# power.net
KiCad netlist of a schematic drawn in Altium Designer
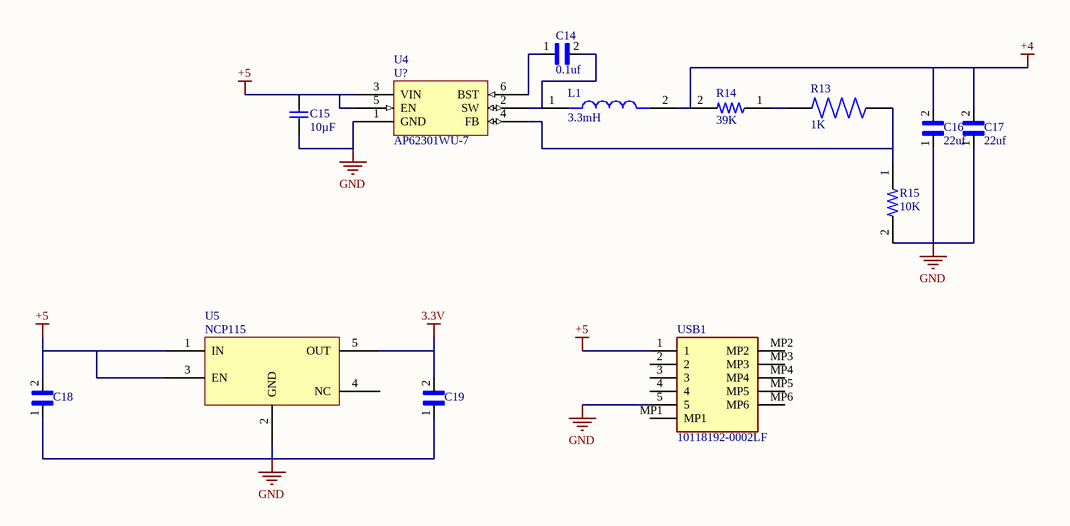
[diagram p0: power.SchDoc]

(export (version "E")
  (design (tool "Eeschema 10.0.6"))
  (components
    (comp (ref "C14")
      (value "0.1uf")
      (footprint "CAPC1608X90N")
      (description "Cap Ceramic 0.1uF 25V Y5V -20% to 80% SMD 0603 85C T/R")
      (fields (field (name "MP") "06033G104ZAT4A") (field (name "MF") "{'manufacturer': u'AVX'}"))
      (libsource (lib "SnapEDA_Library") (part "06033G104ZAT4A"))
    )
    (comp (ref "C15")
      (value "10µF")
      (footprint "CAP_0603")
      (description "10µF 10V Ceramic Capacitor X5R 0603 (1608 Metric) 0.063\" L x 0.031\" W (1.60mm x 0.80mm)")
      (fields
        (field (name "MANUFACTURER") "Samsung Electronics")
        (field (name "PART NUMBER") "CL10A106KP8NNNC")
      )
      (libsource (lib "apollo2-amaph1kk-kbr-brd") (part "CL10A106KP8NNNC"))
    )
    (comp (ref "C16")
      (value "22uf")
      (footprint "CAPC1608X100N")
      (description "Cap Ceramic 22uF 4V X5R 20% SMD 0603 85C T/R")
      (fields (field (name "MF") "{'manufacturer': u'Murata'}") (field (name "MP") "GRM188R60G226MEA0D"))
      (libsource (lib "SnapEDA_Library") (part "GRM188R60G226MEA0D"))
    )
    (comp (ref "C17")
      (value "22uf")
      (footprint "CAPC1608X100N")
      (description "Cap Ceramic 22uF 4V X5R 20% SMD 0603 85C T/R")
      (fields (field (name "MF") "{'manufacturer': u'Murata'}") (field (name "MP") "GRM188R60G226MEA0D"))
      (libsource (lib "SnapEDA_Library") (part "GRM188R60G226MEA0D"))
    )
    (comp (ref "C18")
      (value "06033G104ZAT4A")
      (footprint "CAPC1608X90N")
      (description "Cap Ceramic 0.1uF 25V Y5V -20% to 80% SMD 0603 85C T/R")
      (fields (field (name "MF") "{'manufacturer': u'AVX'}"))
      (libsource (lib "") (part "06033G104ZAT4A_1"))
    )
    (comp (ref "C19")
      (value "06033G104ZAT4A")
      (footprint "CAPC1608X90N")
      (description "Cap Ceramic 0.1uF 25V Y5V -20% to 80% SMD 0603 85C T/R")
      (fields (field (name "MF") "{'manufacturer': u'AVX'}"))
      (libsource (lib "") (part "06033G104ZAT4A_1"))
    )
    (comp (ref "L1")
      (value "3.3mH")
      (footprint "IND_VLS6045AF-3R3N")
      (fields (field (name "MF") "{'manufacturer': u'TDK Corporation'}") (field (name "MP") "VLS6045AF-3R3N"))
      (libsource (lib "SnapEDA_Library") (part "VLS6045AF-3R3N"))
    )
    (comp (ref "R13")
      (value "1K")
      (footprint "RESC1608X55N")
      (description "Resistor; Thick Film; Res 1 Kilohms; Pwr-Rtg 0.1 W; Tol 1%; SMT; 0603")
      (fields (field (name "MP") "CR0603-FX-1001ELF") (field (name "MF") "{'manufacturer': u'Bourns'}"))
      (libsource (lib "SnapEDA_Library") (part "CR0603-FX-1001ELF"))
    )
    (comp (ref "R14")
      (value "39K")
      (footprint "RESC1607X60N")
      (description "Res Thick Film 1.6 x 0.8 mm 39K Ohm 1% 0.1W(1/10W) 100ppm/ C Molded SMD Paper T/R")
      (fields (field (name "MF") "{'manufacturer': u'Yageo'}") (field (name "MP") "RC0603FR-0739KL"))
      (libsource (lib "SnapEDA_Library") (part "RC0603FR-0739KL"))
    )
    (comp (ref "R15")
      (value "10K")
      (footprint "RESC1607X60N")
      (description "YAGEO RC0603FR-0710KL / RESISTOR 10K 1/10W 1% 0603 YAG")
      (fields (field (name "MF") "{'manufacturer': u'Yageo'}") (field (name "MP") "RC0603FR-0710KL"))
      (libsource (lib "SnapEDA_Library") (part "RC0603FR-0710KL"))
    )
    (comp (ref "U4")
      (value "AP62301WU-7")
      (footprint "AP62301WU-7")
      (libsource (lib "AP62301WU-7") (part "AP62301WU-7"))
    )
    (comp (ref "U5")
      (value "NCP115ASN330T2G")
      (footprint "NCP115")
      (libsource (lib "NCP115") (part "NCP115ASN330T2G"))
    )
    (comp (ref "USB1")
      (value "10118192-0002LF")
      (footprint "mouser_layout_lib:101181920002LF")
      (description "Connector")
      (fields (field (name "MOUSER PART NUMBER") "649-10118192-0002LF"))
      (libsource (lib "*") (part "10118192-0002LF"))
    )
  )
  (nets
    (net (code "1") (name "+4") (class "Default")
      (node (ref "C16") (pin "2") (pinfunction "2_2") (pintype "passive"))
      (node (ref "C17") (pin "2") (pinfunction "2_2") (pintype "passive"))
      (node (ref "L1") (pin "2") (pinfunction "2_2") (pintype "passive"))
      (node (ref "R14") (pin "2") (pinfunction "2_2") (pintype "passive"))
    )
    (net (code "2") (name "+5") (class "Default")
      (node (ref "C15") (pin "1") (pinfunction "1_1") (pintype "passive"))
      (node (ref "C18") (pin "2") (pinfunction "2_2") (pintype "passive"))
      (node (ref "U4") (pin "3") (pinfunction "VIN_3") (pintype "power_in"))
      (node (ref "U4") (pin "5") (pinfunction "EN_5") (pintype "input"))
      (node (ref "U5") (pin "1") (pinfunction "IN_1") (pintype "passive"))
      (node (ref "U5") (pin "3") (pinfunction "EN_3") (pintype "passive"))
      (node (ref "USB1") (pin "1") (pinfunction "1_1") (pintype "passive"))
    )
    (net (code "3") (name "3.3V") (class "Default")
      (node (ref "C19") (pin "2") (pinfunction "2_2") (pintype "passive"))
      (node (ref "U5") (pin "5") (pinfunction "OUT_5") (pintype "passive"))
    )
    (net (code "4") (name "GND") (class "Default")
      (node (ref "C15") (pin "2") (pinfunction "2_2") (pintype "passive"))
      (node (ref "C16") (pin "1") (pinfunction "1_1") (pintype "passive"))
      (node (ref "C17") (pin "1") (pinfunction "1_1") (pintype "passive"))
      (node (ref "C18") (pin "1") (pinfunction "1_1") (pintype "passive"))
      (node (ref "C19") (pin "1") (pinfunction "1_1") (pintype "passive"))
      (node (ref "R15") (pin "2") (pinfunction "2_2") (pintype "passive"))
      (node (ref "U4") (pin "1") (pinfunction "GND_1") (pintype "power_in"))
      (node (ref "U5") (pin "2") (pinfunction "GND_2") (pintype "passive"))
      (node (ref "USB1") (pin "5") (pinfunction "5_5") (pintype "passive"))
    )
    (net (code "5") (name "Net-(R13-Pad2)") (class "Default")
      (node (ref "R13") (pin "2") (pinfunction "2_2") (pintype "passive"))
      (node (ref "R14") (pin "1") (pinfunction "1_1") (pintype "passive"))
    )
    (net (code "6") (name "Net-(U4-BST)") (class "Default")
      (node (ref "C14") (pin "1") (pinfunction "1_1") (pintype "passive"))
      (node (ref "U4") (pin "6") (pinfunction "BST_6") (pintype "input"))
    )
    (net (code "7") (name "Net-(U4-FB)") (class "Default")
      (node (ref "R13") (pin "1") (pinfunction "1_1") (pintype "passive"))
      (node (ref "R15") (pin "1") (pinfunction "1_1") (pintype "passive"))
      (node (ref "U4") (pin "4") (pinfunction "FB_4") (pintype "bidirectional"))
    )
    (net (code "8") (name "Net-(U4-SW)") (class "Default")
      (node (ref "C14") (pin "2") (pinfunction "2_2") (pintype "passive"))
      (node (ref "L1") (pin "1") (pinfunction "1_1") (pintype "passive"))
      (node (ref "U4") (pin "2") (pinfunction "SW_2") (pintype "bidirectional"))
    )
    (net (code "9") (name "unconnected-(U5-NC-Pad4)") (class "Default")
      (node (ref "U5") (pin "4") (pinfunction "NC_4") (pintype "passive"))
    )
    (net (code "10") (name "unconnected-(USB1-Pad2)") (class "Default")
      (node (ref "USB1") (pin "2") (pinfunction "2_2") (pintype "passive"))
    )
    (net (code "11") (name "unconnected-(USB1-Pad3)") (class "Default")
      (node (ref "USB1") (pin "3") (pinfunction "3_3") (pintype "passive"))
    )
    (net (code "12") (name "unconnected-(USB1-Pad4)") (class "Default")
      (node (ref "USB1") (pin "4") (pinfunction "4_4") (pintype "passive"))
    )
    (net (code "13") (name "unconnected-(USB1-PadMP1)") (class "Default")
      (node (ref "USB1") (pin "MP1") (pinfunction "MP1_MP1") (pintype "passive"))
    )
    (net (code "14") (name "unconnected-(USB1-PadMP2)") (class "Default")
      (node (ref "USB1") (pin "MP2") (pinfunction "MP2_MP2") (pintype "passive"))
    )
    (net (code "15") (name "unconnected-(USB1-PadMP3)") (class "Default")
      (node (ref "USB1") (pin "MP3") (pinfunction "MP3_MP3") (pintype "passive"))
    )
    (net (code "16") (name "unconnected-(USB1-PadMP4)") (class "Default")
      (node (ref "USB1") (pin "MP4") (pinfunction "MP4_MP4") (pintype "passive"))
    )
    (net (code "17") (name "unconnected-(USB1-PadMP5)") (class "Default")
      (node (ref "USB1") (pin "MP5") (pinfunction "MP5_MP5") (pintype "passive"))
    )
    (net (code "18") (name "unconnected-(USB1-PadMP6)") (class "Default")
      (node (ref "USB1") (pin "MP6") (pinfunction "MP6_MP6") (pintype "passive"))
    )
  )
)
